# IntrusionNode_v2.net
KiCad netlist of a schematic drawn in EAGLE
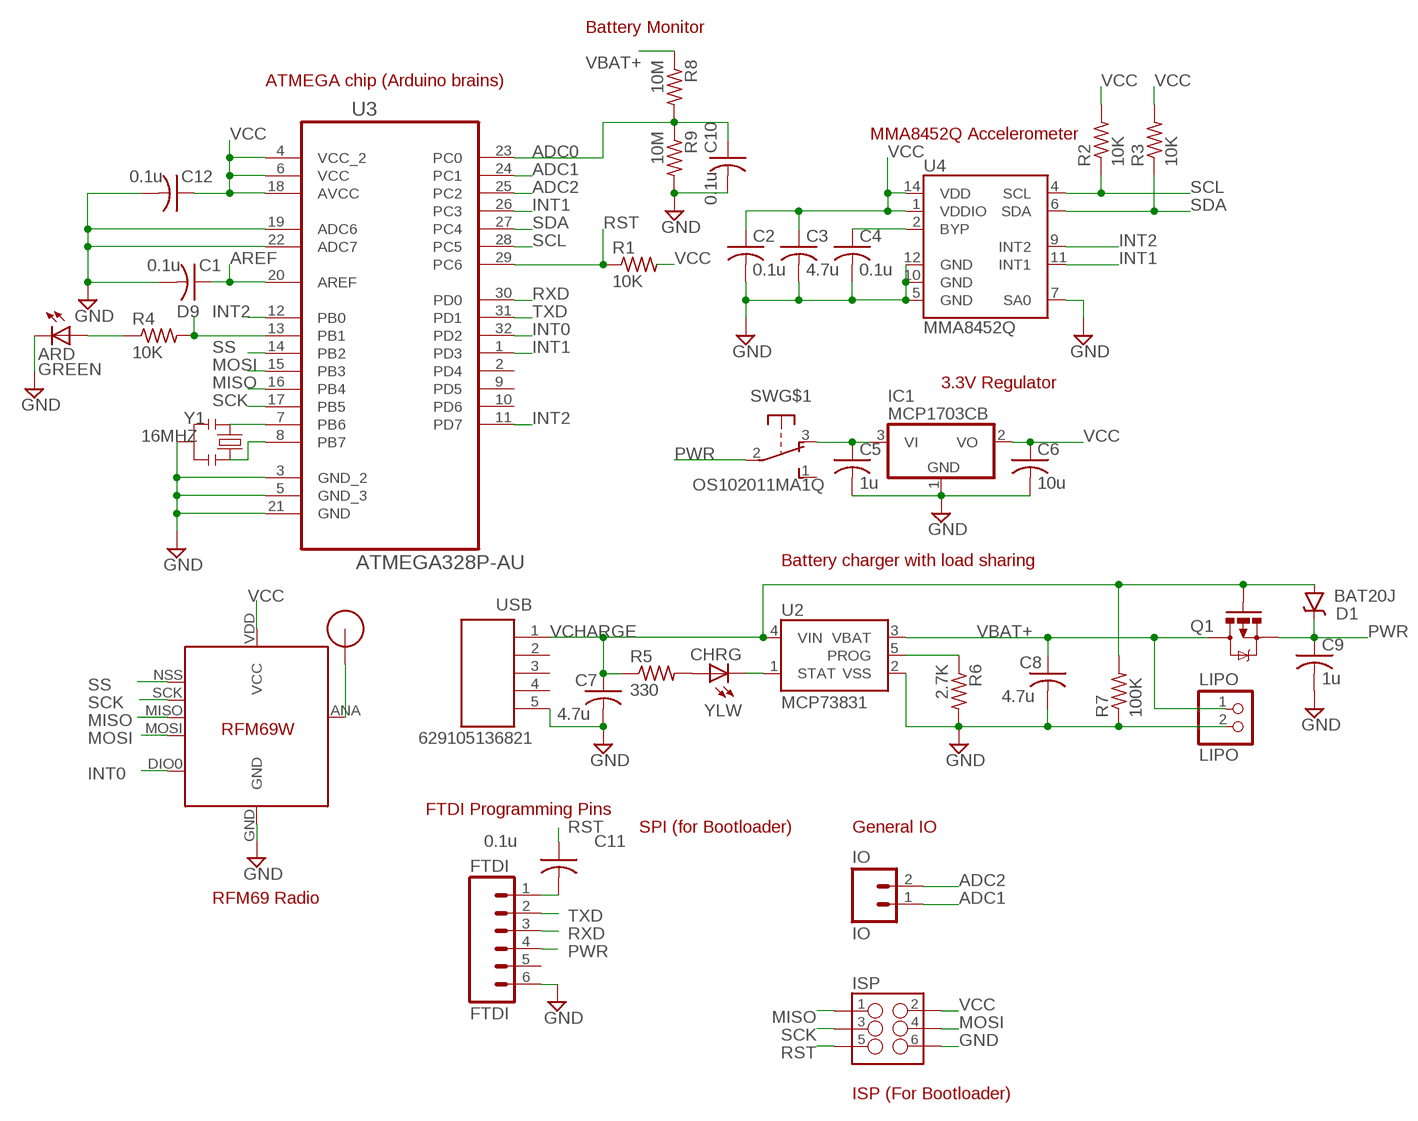
[diagram p0: schematic, sheet 1]

(export (version "E")
  (design (tool "Eeschema 10.0.6"))
  (components
    (comp (ref "ANT")
      (value "RFM12B_ANTENNA")
      (footprint "eagle-import:RFM12B-ANTENNA")
      (libsource (lib "eagle-import") (part "RFM12B_ANTENNA"))
    )
    (comp (ref "ARD")
      (value "GREEN")
      (footprint "eagle-import:CHIPLED_0805")
      (fields (field (name "PARTNO") "LG R971-KN-1"))
      (libsource (lib "eagle-import") (part "LEDCHIPLED_0805"))
    )
    (comp (ref "C1")
      (value "0.1u")
      (footprint "eagle-import:C0805")
      (fields (field (name "PARTNO") "CL21B104KBCNNNC"))
      (libsource (lib "eagle-import") (part "C-USC0805"))
    )
    (comp (ref "C2")
      (value "0.1u")
      (footprint "eagle-import:C0805")
      (fields (field (name "PARTNO") "CL21B104KBCNNNC"))
      (libsource (lib "eagle-import") (part "C-USC0805"))
    )
    (comp (ref "C3")
      (value "4.7u")
      (footprint "eagle-import:C0805")
      (fields (field (name "PARTNO") "CL21A475KPFNNNE"))
      (libsource (lib "eagle-import") (part "C-USC0805"))
    )
    (comp (ref "C4")
      (value "0.1u")
      (footprint "eagle-import:C0805")
      (fields (field (name "PARTNO") "CL21B104KBCNNNC"))
      (libsource (lib "eagle-import") (part "C-USC0805"))
    )
    (comp (ref "C5")
      (value "1u")
      (footprint "eagle-import:C0805")
      (fields (field (name "PARTNO") "CL21B105KPFNNNE"))
      (libsource (lib "eagle-import") (part "C-USC0805"))
    )
    (comp (ref "C6")
      (value "10u")
      (footprint "eagle-import:C0805")
      (fields (field (name "PARTNO") "CL21B106KPQNNNE"))
      (libsource (lib "eagle-import") (part "C-USC0805"))
    )
    (comp (ref "C7")
      (value "4.7u")
      (footprint "eagle-import:C0805")
      (fields (field (name "PARTNO") "CL21A475KPFNNNE"))
      (libsource (lib "eagle-import") (part "C-USC0805"))
    )
    (comp (ref "C8")
      (value "4.7u")
      (footprint "eagle-import:C0805")
      (fields (field (name "PARTNO") "CL21A475KPFNNNE"))
      (libsource (lib "eagle-import") (part "C-USC0805"))
    )
    (comp (ref "C9")
      (value "1u")
      (footprint "eagle-import:C0805")
      (fields (field (name "PARTNO") "CL21B105KPFNNNE"))
      (libsource (lib "eagle-import") (part "C-USC0805"))
    )
    (comp (ref "C10")
      (value "0.1u")
      (footprint "eagle-import:C0805")
      (fields (field (name "PARTNO") "CL21B104KBCNNNC"))
      (libsource (lib "eagle-import") (part "C-USC0805"))
    )
    (comp (ref "C11")
      (value "0.1u")
      (footprint "eagle-import:C0805")
      (fields (field (name "PARTNO") "CL21B104KBCNNNC"))
      (libsource (lib "eagle-import") (part "C-USC0805"))
    )
    (comp (ref "C12")
      (value "0.1u")
      (footprint "eagle-import:C0805")
      (fields (field (name "PARTNO") "CL21B104KBCNNNC"))
      (libsource (lib "eagle-import") (part "C-USC0805"))
    )
    (comp (ref "CHRG")
      (value "YLW")
      (footprint "eagle-import:CHIPLED_0805")
      (fields (field (name "PARTNO") "LY R976-PS-36"))
      (libsource (lib "eagle-import") (part "LEDCHIPLED_0805"))
    )
    (comp (ref "D1")
      (value "BAT20J")
      (footprint "eagle-import:SOD-323")
      (fields (field (name "PARTNO") "BAT20JFILM"))
      (libsource (lib "eagle-import") (part "DIODE-SCHOTTKY-BAT20J"))
    )
    (comp (ref "FTDI")
      (value "FTDI")
      (footprint "eagle-import:1X06_LOCK_LONGPADS")
      (fields (field (name "PARTNO") "0022284363"))
      (libsource (lib "eagle-import") (part "M06LOCK_LONGPADS"))
    )
    (comp (ref "IC1")
      (value "MCP1703CB")
      (footprint "eagle-import:SOT23")
      (fields (field (name "PARTNO") "MCP1703T-3302E/CB"))
      (libsource (lib "eagle-import") (part "MCP1703CB"))
    )
    (comp (ref "IO")
      (value "IO")
      (footprint "eagle-import:1X02_LOCK_LONGPADS")
      (fields (field (name "PARTNO") "0022284363"))
      (libsource (lib "eagle-import") (part "M02LOCK_LONGPADS"))
    )
    (comp (ref "ISP")
      (value "M03X2NO_SILK")
      (footprint "eagle-import:2X3-NS")
      (fields (field (name "PARTNO") "0010897060"))
      (libsource (lib "eagle-import") (part "M03X2NO_SILK"))
    )
    (comp (ref "LIPO")
      (value "LIPO")
      (footprint "eagle-import:JST-PH-2-SMT-RA")
      (fields (field (name "PARTNO") "S2B-PH-SM4-TB(LF)(SN)"))
      (libsource (lib "eagle-import") (part "JST_2PIN-SMT-RA"))
    )
    (comp (ref "Q1")
      (value "MOSFET-PCHANNELSMD")
      (footprint "eagle-import:SOT23-3")
      (fields (field (name "PARTNO") "PMV48XP,215"))
      (libsource (lib "eagle-import") (part "MOSFET-PCHANNELSMD"))
    )
    (comp (ref "R1")
      (value "10K")
      (footprint "eagle-import:R0805")
      (fields (field (name "PARTNO") "RC2012J103CS"))
      (libsource (lib "eagle-import") (part "R-US_R0805"))
    )
    (comp (ref "R2")
      (value "10K")
      (footprint "eagle-import:R0805")
      (fields (field (name "PARTNO") "RC2012J103CS"))
      (libsource (lib "eagle-import") (part "R-US_R0805"))
    )
    (comp (ref "R3")
      (value "10K")
      (footprint "eagle-import:R0805")
      (fields (field (name "PARTNO") "RC2012J103CS"))
      (libsource (lib "eagle-import") (part "R-US_R0805"))
    )
    (comp (ref "R4")
      (value "10K")
      (footprint "eagle-import:R0805")
      (fields (field (name "PARTNO") "RC2012J103CS"))
      (libsource (lib "eagle-import") (part "R-US_R0805"))
    )
    (comp (ref "R5")
      (value "330")
      (footprint "eagle-import:R0805")
      (fields (field (name "PARTNO") "RC2012J331CS"))
      (libsource (lib "eagle-import") (part "R-US_R0805"))
    )
    (comp (ref "R6")
      (value "2.7K")
      (footprint "eagle-import:R0805")
      (fields (field (name "PARTNO") "RC2012J272CS"))
      (libsource (lib "eagle-import") (part "R-US_R0805"))
    )
    (comp (ref "R7")
      (value "100K")
      (footprint "eagle-import:R0805")
      (fields (field (name "PARTNO") "RC2012J104CS"))
      (libsource (lib "eagle-import") (part "R-US_R0805"))
    )
    (comp (ref "R8")
      (value "10M")
      (footprint "eagle-import:R0805")
      (fields (field (name "PARTNO") "RC2012F106CS"))
      (libsource (lib "eagle-import") (part "R-US_R0805"))
    )
    (comp (ref "R9")
      (value "10M")
      (footprint "eagle-import:R0805")
      (fields (field (name "PARTNO") "RC2012F106CS"))
      (libsource (lib "eagle-import") (part "R-US_R0805"))
    )
    (comp (ref "SW")
      (value "OS102011MA1Q")
      (footprint "eagle-import:OS102011MA1Q")
      (fields (field (name "PARTNO") "OS102011MA1QN1"))
      (libsource (lib "eagle-import") (part "OS102011MA1Q"))
    )
    (comp (ref "U1")
      (value "RFM69")
      (footprint "eagle-import:RFM69W-MINPADS")
      (fields (field (name "PARTNO") "RFM69W"))
      (libsource (lib "eagle-import") (part "RFM69"))
    )
    (comp (ref "U2")
      (value "MCP73831")
      (footprint "eagle-import:SOT23-5")
      (fields (field (name "PARTNO") "MCP73831T-2ATI/OT"))
      (libsource (lib "eagle-import") (part "MCP73831"))
    )
    (comp (ref "U3")
      (value "ATMEGA328P-AU")
      (footprint "eagle-import:QFP80P900X900X120-32N")
      (fields (field (name "PARTNO") "ATMEGA328P-AUR"))
      (libsource (lib "eagle-import") (part "ATMEGA328P-AU"))
    )
    (comp (ref "U4")
      (value "MMA8452Q")
      (footprint "eagle-import:QFN-16_0.5MM")
      (fields (field (name "PARTNO") "MMA8452QT"))
      (libsource (lib "eagle-import") (part "MMA8452Q"))
    )
    (comp (ref "USB")
      (value "629105136821")
      (footprint "eagle-import:629105136821")
      (libsource (lib "eagle-import") (part "629105136821"))
    )
    (comp (ref "Y1")
      (value "16MHZ")
      (footprint "eagle-import:X3-SMD-3.6X1.3X0.8MM")
      (fields (field (name "MPN") "CSTCE16M0V53-R0"))
      (libsource (lib "eagle-import") (part "SMD-RESONATOR-16MHZ-15PF-0.5%-40R(3P-3.2X1.3MM)"))
    )
  )
  (nets
    (net (code "1") (name "/ADC0") (class "Default")
      (node (ref "C10") (pin "1") (pinfunction "1_1") (pintype "passive"))
      (node (ref "R8") (pin "2") (pinfunction "2_2") (pintype "passive"))
      (node (ref "R9") (pin "1") (pinfunction "1_1") (pintype "passive"))
      (node (ref "U3") (pin "23") (pinfunction "PC0_23") (pintype "bidirectional"))
    )
    (net (code "2") (name "/ADC1") (class "Default")
      (node (ref "IO") (pin "1") (pinfunction "1_1") (pintype "passive"))
      (node (ref "U3") (pin "24") (pinfunction "PC1_24") (pintype "bidirectional"))
    )
    (net (code "3") (name "/ADC2") (class "Default")
      (node (ref "IO") (pin "2") (pinfunction "2_2") (pintype "passive"))
      (node (ref "U3") (pin "25") (pinfunction "PC2_25") (pintype "bidirectional"))
    )
    (net (code "4") (name "/AREF") (class "Default")
      (node (ref "C1") (pin "1") (pinfunction "1_1") (pintype "passive"))
      (node (ref "U3") (pin "20") (pinfunction "AREF_20") (pintype "input"))
    )
    (net (code "5") (name "/D9") (class "Default")
      (node (ref "R4") (pin "2") (pinfunction "2_2") (pintype "passive"))
      (node (ref "U3") (pin "13") (pinfunction "PB1_13") (pintype "bidirectional"))
    )
    (net (code "6") (name "/INT0") (class "Default")
      (node (ref "U1") (pin "DIO0") (pinfunction "DIO0_DIO0") (pintype "open_collector"))
      (node (ref "U3") (pin "32") (pinfunction "PD2_32") (pintype "bidirectional"))
    )
    (net (code "7") (name "/INT1") (class "Default")
      (node (ref "U3") (pin "1") (pinfunction "PD3_1") (pintype "bidirectional"))
      (node (ref "U3") (pin "26") (pinfunction "PC3_26") (pintype "bidirectional"))
      (node (ref "U4") (pin "11") (pinfunction "INT1_11") (pintype "bidirectional"))
    )
    (net (code "8") (name "/INT2") (class "Default")
      (node (ref "U3") (pin "11") (pinfunction "PD7_11") (pintype "bidirectional"))
      (node (ref "U3") (pin "12") (pinfunction "PB0_12") (pintype "bidirectional"))
      (node (ref "U4") (pin "9") (pinfunction "INT2_9") (pintype "bidirectional"))
    )
    (net (code "9") (name "/MISO") (class "Default")
      (node (ref "ISP") (pin "1") (pinfunction "1_1") (pintype "bidirectional"))
      (node (ref "U1") (pin "MISO") (pinfunction "MISO_MISO") (pintype "input"))
      (node (ref "U3") (pin "16") (pinfunction "PB4_16") (pintype "bidirectional"))
    )
    (net (code "10") (name "/MOSI") (class "Default")
      (node (ref "ISP") (pin "4") (pinfunction "4_4") (pintype "bidirectional"))
      (node (ref "U1") (pin "MOSI") (pinfunction "MOSI_MOSI") (pintype "output"))
      (node (ref "U3") (pin "15") (pinfunction "PB3_15") (pintype "bidirectional"))
    )
    (net (code "11") (name "/PWR") (class "Default")
      (node (ref "C9") (pin "1") (pinfunction "1_1") (pintype "passive"))
      (node (ref "D1") (pin "C") (pinfunction "C_C") (pintype "passive"))
      (node (ref "FTDI") (pin "4") (pinfunction "4_4") (pintype "passive"))
      (node (ref "Q1") (pin "2") (pinfunction "S_2") (pintype "passive"))
      (node (ref "SW") (pin "2") (pinfunction "P_2") (pintype "passive"))
    )
    (net (code "12") (name "/RST") (class "Default")
      (node (ref "C11") (pin "1") (pinfunction "1_1") (pintype "passive"))
      (node (ref "ISP") (pin "5") (pinfunction "5_5") (pintype "bidirectional"))
      (node (ref "R1") (pin "1") (pinfunction "1_1") (pintype "passive"))
      (node (ref "U3") (pin "29") (pinfunction "PC6_29") (pintype "bidirectional"))
    )
    (net (code "13") (name "/RXD") (class "Default")
      (node (ref "FTDI") (pin "3") (pinfunction "3_3") (pintype "passive"))
      (node (ref "U3") (pin "30") (pinfunction "PD0_30") (pintype "bidirectional"))
    )
    (net (code "14") (name "/SCK") (class "Default")
      (node (ref "ISP") (pin "3") (pinfunction "3_3") (pintype "bidirectional"))
      (node (ref "U1") (pin "SCK") (pinfunction "SCK_SCK") (pintype "input"))
      (node (ref "U3") (pin "17") (pinfunction "PB5_17") (pintype "bidirectional"))
    )
    (net (code "15") (name "/SCL") (class "Default")
      (node (ref "R2") (pin "1") (pinfunction "1_1") (pintype "passive"))
      (node (ref "U3") (pin "28") (pinfunction "PC5_28") (pintype "bidirectional"))
      (node (ref "U4") (pin "4") (pinfunction "SCL_4") (pintype "bidirectional"))
    )
    (net (code "16") (name "/SDA") (class "Default")
      (node (ref "R3") (pin "1") (pinfunction "1_1") (pintype "passive"))
      (node (ref "U3") (pin "27") (pinfunction "PC4_27") (pintype "bidirectional"))
      (node (ref "U4") (pin "6") (pinfunction "SDA_6") (pintype "bidirectional"))
    )
    (net (code "17") (name "/SS") (class "Default")
      (node (ref "U1") (pin "NSS") (pinfunction "SEL_NSS") (pintype "input"))
      (node (ref "U3") (pin "14") (pinfunction "PB2_14") (pintype "bidirectional"))
    )
    (net (code "18") (name "/TXD") (class "Default")
      (node (ref "FTDI") (pin "2") (pinfunction "2_2") (pintype "passive"))
      (node (ref "U3") (pin "31") (pinfunction "PD1_31") (pintype "bidirectional"))
    )
    (net (code "19") (name "/VBAT+") (class "Default")
      (node (ref "C8") (pin "1") (pinfunction "1_1") (pintype "passive"))
      (node (ref "LIPO") (pin "1") (pinfunction "2_1") (pintype "passive"))
      (node (ref "Q1") (pin "3") (pinfunction "D_3") (pintype "passive"))
      (node (ref "R8") (pin "1") (pinfunction "1_1") (pintype "passive"))
      (node (ref "U2") (pin "3") (pinfunction "VBAT_3") (pintype "power_in"))
    )
    (net (code "20") (name "/VCC") (class "Default")
      (node (ref "C12") (pin "1") (pinfunction "1_1") (pintype "passive"))
      (node (ref "C2") (pin "1") (pinfunction "1_1") (pintype "passive"))
      (node (ref "C3") (pin "1") (pinfunction "1_1") (pintype "passive"))
      (node (ref "C6") (pin "1") (pinfunction "1_1") (pintype "passive"))
      (node (ref "IC1") (pin "2") (pinfunction "VO_2") (pintype "passive"))
      (node (ref "ISP") (pin "2") (pinfunction "2_2") (pintype "bidirectional"))
      (node (ref "R1") (pin "2") (pinfunction "2_2") (pintype "passive"))
      (node (ref "R2") (pin "2") (pinfunction "2_2") (pintype "passive"))
      (node (ref "R3") (pin "2") (pinfunction "2_2") (pintype "passive"))
      (node (ref "U1") (pin "VDD") (pinfunction "VCC_VDD") (pintype "power_in"))
      (node (ref "U3") (pin "18") (pinfunction "AVCC_18") (pintype "power_in"))
      (node (ref "U3") (pin "4") (pinfunction "VCC_2_4") (pintype "power_in"))
      (node (ref "U3") (pin "6") (pinfunction "VCC_6") (pintype "power_in"))
      (node (ref "U4") (pin "1") (pinfunction "VDDIO_1") (pintype "bidirectional"))
      (node (ref "U4") (pin "14") (pinfunction "VDD_14") (pintype "bidirectional"))
    )
    (net (code "21") (name "/VCHARGE") (class "Default")
      (node (ref "C7") (pin "1") (pinfunction "1_1") (pintype "passive"))
      (node (ref "D1") (pin "A") (pinfunction "A_A") (pintype "passive"))
      (node (ref "Q1") (pin "1") (pinfunction "G_1") (pintype "passive"))
      (node (ref "R5") (pin "1") (pinfunction "1_1") (pintype "passive"))
      (node (ref "R7") (pin "2") (pinfunction "2_2") (pintype "passive"))
      (node (ref "U2") (pin "4") (pinfunction "VIN_4") (pintype "power_in"))
      (node (ref "USB") (pin "1") (pinfunction "1_1") (pintype "passive"))
    )
    (net (code "22") (name "GND") (class "Default")
      (node (ref "ARD") (pin "C") (pinfunction "C_C") (pintype "passive"))
      (node (ref "C1") (pin "2") (pinfunction "2_2") (pintype "passive"))
      (node (ref "C10") (pin "2") (pinfunction "2_2") (pintype "passive"))
      (node (ref "C12") (pin "2") (pinfunction "2_2") (pintype "passive"))
      (node (ref "C2") (pin "2") (pinfunction "2_2") (pintype "passive"))
      (node (ref "C3") (pin "2") (pinfunction "2_2") (pintype "passive"))
      (node (ref "C4") (pin "2") (pinfunction "2_2") (pintype "passive"))
      (node (ref "C5") (pin "2") (pinfunction "2_2") (pintype "passive"))
      (node (ref "C6") (pin "2") (pinfunction "2_2") (pintype "passive"))
      (node (ref "C7") (pin "2") (pinfunction "2_2") (pintype "passive"))
      (node (ref "C8") (pin "2") (pinfunction "2_2") (pintype "passive"))
      (node (ref "C9") (pin "2") (pinfunction "2_2") (pintype "passive"))
      (node (ref "FTDI") (pin "6") (pinfunction "6_6") (pintype "passive"))
      (node (ref "IC1") (pin "1") (pinfunction "GND_1") (pintype "passive"))
      (node (ref "ISP") (pin "6") (pinfunction "6_6") (pintype "bidirectional"))
      (node (ref "LIPO") (pin "2") (pinfunction "1_2") (pintype "passive"))
      (node (ref "R6") (pin "2") (pinfunction "2_2") (pintype "passive"))
      (node (ref "R7") (pin "1") (pinfunction "1_1") (pintype "passive"))
      (node (ref "R9") (pin "2") (pinfunction "2_2") (pintype "passive"))
      (node (ref "U1") (pin "GND") (pinfunction "GND_GND") (pintype "power_in"))
      (node (ref "U2") (pin "2") (pinfunction "VSS_2") (pintype "power_in"))
      (node (ref "U3") (pin "19") (pinfunction "ADC6_19") (pintype "input"))
      (node (ref "U3") (pin "21") (pinfunction "GND_21") (pintype "passive"))
      (node (ref "U3") (pin "22") (pinfunction "ADC7_22") (pintype "input"))
      (node (ref "U3") (pin "3") (pinfunction "GND_2_3") (pintype "passive"))
      (node (ref "U3") (pin "5") (pinfunction "GND_3_5") (pintype "passive"))
      (node (ref "U4") (pin "10") (pinfunction "GND_10") (pintype "bidirectional"))
      (node (ref "U4") (pin "12") (pinfunction "GND_12") (pintype "bidirectional"))
      (node (ref "U4") (pin "5") (pinfunction "GND_5") (pintype "bidirectional"))
      (node (ref "U4") (pin "7") (pinfunction "SA0_7") (pintype "bidirectional"))
      (node (ref "USB") (pin "5") (pinfunction "5_5") (pintype "passive"))
      (node (ref "Y1") (pin "2") (pinfunction "2_2") (pintype "passive"))
    )
    (net (code "23") (name "Net-(ANT-1)") (class "Default")
      (node (ref "ANT") (pin "P$1") (pinfunction "1_P$1") (pintype "bidirectional"))
      (node (ref "U1") (pin "ANA") (pinfunction "ANT_ANA") (pintype "passive"))
    )
    (net (code "24") (name "Net-(ARD-PadA)") (class "Default")
      (node (ref "ARD") (pin "A") (pinfunction "A_A") (pintype "passive"))
      (node (ref "R4") (pin "1") (pinfunction "1_1") (pintype "passive"))
    )
    (net (code "25") (name "Net-(C11-Pad2)") (class "Default")
      (node (ref "C11") (pin "2") (pinfunction "2_2") (pintype "passive"))
      (node (ref "FTDI") (pin "1") (pinfunction "1_1") (pintype "passive"))
    )
    (net (code "26") (name "Net-(CHRG-PadA)") (class "Default")
      (node (ref "CHRG") (pin "A") (pinfunction "A_A") (pintype "passive"))
      (node (ref "R5") (pin "2") (pinfunction "2_2") (pintype "passive"))
    )
    (net (code "27") (name "Net-(IC1-VI)") (class "Default")
      (node (ref "C5") (pin "1") (pinfunction "1_1") (pintype "passive"))
      (node (ref "IC1") (pin "3") (pinfunction "VI_3") (pintype "input"))
      (node (ref "SW") (pin "3") (pinfunction "O_3") (pintype "passive"))
    )
    (net (code "28") (name "Net-(U2-PROG)") (class "Default")
      (node (ref "R6") (pin "1") (pinfunction "1_1") (pintype "passive"))
      (node (ref "U2") (pin "5") (pinfunction "PROG_5") (pintype "input"))
    )
    (net (code "29") (name "Net-(U2-STAT)") (class "Default")
      (node (ref "CHRG") (pin "C") (pinfunction "C_C") (pintype "passive"))
      (node (ref "U2") (pin "1") (pinfunction "STAT_1") (pintype "output"))
    )
    (net (code "30") (name "Net-(U3-PB6)") (class "Default")
      (node (ref "U3") (pin "7") (pinfunction "PB6_7") (pintype "bidirectional"))
      (node (ref "Y1") (pin "1") (pinfunction "1_1") (pintype "passive"))
    )
    (net (code "31") (name "Net-(U3-PB7)") (class "Default")
      (node (ref "U3") (pin "8") (pinfunction "PB7_8") (pintype "bidirectional"))
      (node (ref "Y1") (pin "3") (pinfunction "3_3") (pintype "passive"))
    )
    (net (code "32") (name "Net-(U4-BYP)") (class "Default")
      (node (ref "C4") (pin "1") (pinfunction "1_1") (pintype "passive"))
      (node (ref "U4") (pin "2") (pinfunction "BYP_2") (pintype "bidirectional"))
    )
    (net (code "33") (name "unconnected-(FTDI-Pad5)") (class "Default")
      (node (ref "FTDI") (pin "5") (pinfunction "5_5") (pintype "passive"))
    )
    (net (code "34") (name "unconnected-(SWA-S-Pad1)") (class "Default")
      (node (ref "SW") (pin "1") (pinfunction "S_1") (pintype "passive"))
    )
    (net (code "35") (name "unconnected-(U3-PD4-Pad2)") (class "Default")
      (node (ref "U3") (pin "2") (pinfunction "PD4_2") (pintype "bidirectional"))
    )
    (net (code "36") (name "unconnected-(U3-PD5-Pad9)") (class "Default")
      (node (ref "U3") (pin "9") (pinfunction "PD5_9") (pintype "bidirectional"))
    )
    (net (code "37") (name "unconnected-(U3-PD6-Pad10)") (class "Default")
      (node (ref "U3") (pin "10") (pinfunction "PD6_10") (pintype "bidirectional"))
    )
    (net (code "38") (name "unconnected-(USB-Pad2)") (class "Default")
      (node (ref "USB") (pin "2") (pinfunction "2_2") (pintype "passive"))
    )
    (net (code "39") (name "unconnected-(USB-Pad3)") (class "Default")
      (node (ref "USB") (pin "3") (pinfunction "3_3") (pintype "passive"))
    )
    (net (code "40") (name "unconnected-(USB-Pad4)") (class "Default")
      (node (ref "USB") (pin "4") (pinfunction "4_4") (pintype "passive"))
    )
  )
)
